# 3_Power.net
KiCad netlist of a schematic drawn in Altium Designer
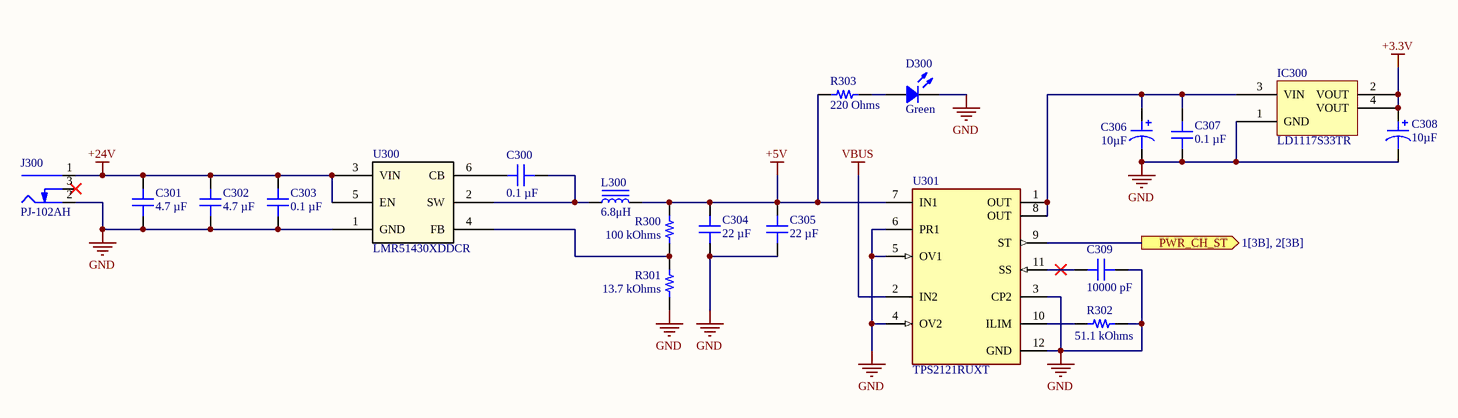
[diagram p0: 3_Power.SchDoc]

(export (version "E")
  (design (tool "Eeschema 10.0.6"))
  (components
    (comp (ref "C300")
      (value "0.1 µF")
      (footprint "CAP 0603_1608")
      (description "CAP CER 0.1UF 25V X7R 0603")
      (fields
        (field (name "PART NUMBER") "CL10B104KA8NNNC")
        (field (name "CAPACITANCE") "0.1 µF")
        (field (name "MANUFACTURER") "Samsung Electro-Mechanics")
      )
      (libsource (lib "Celestial Altium Library - altium_library") (part "Capacitor"))
    )
    (comp (ref "C301")
      (value "4.7 µF")
      (footprint "CAP 1206_3216 - 0.8MM")
      (description "CAP CER 4.7UF 50V X7R 1206")
      (fields
        (field (name "PART NUMBER") "CL31B475KBHNNNE")
        (field (name "CAPACITANCE") "4.7 µF")
        (field (name "MANUFACTURER") "Samsung Electro-Mechanics")
      )
      (libsource (lib "Celestial Altium Library - altium_library") (part "Capacitor"))
    )
    (comp (ref "C302")
      (value "4.7 µF")
      (footprint "CAP 1206_3216 - 0.8MM")
      (description "CAP CER 4.7UF 50V X7R 1206")
      (fields
        (field (name "PART NUMBER") "CL31B475KBHNNNE")
        (field (name "CAPACITANCE") "4.7 µF")
        (field (name "MANUFACTURER") "Samsung Electro-Mechanics")
      )
      (libsource (lib "Celestial Altium Library - altium_library") (part "Capacitor"))
    )
    (comp (ref "C303")
      (value "0.1 µF")
      (footprint "CAP 0603_1608")
      (description "CAP CER 0.1UF 50V X7R 0603")
      (fields
        (field (name "PART NUMBER") "CL10B104KB8NNNC")
        (field (name "CAPACITANCE") "0.1 µF")
        (field (name "MANUFACTURER") "Samsung Electro-Mechanics")
      )
      (libsource (lib "Celestial Altium Library - altium_library") (part "Capacitor"))
    )
    (comp (ref "C304")
      (value "22 µF")
      (footprint "CAP 1210_3225 - 1MM")
      (description "CAP CER 22UF 25V X7R 1210")
      (fields
        (field (name "PART NUMBER") "CL32B226KAJNNNE")
        (field (name "MANUFACTURER") "Samsung Electro-Mechanics")
      )
      (libsource (lib "Celestial Altium Library - altium_library") (part "Capacitor"))
    )
    (comp (ref "C305")
      (value "22 µF")
      (footprint "CAP 1210_3225 - 1MM")
      (description "CAP CER 22UF 25V X7R 1210")
      (fields
        (field (name "PART NUMBER") "CL32B226KAJNNNE")
        (field (name "MANUFACTURER") "Samsung Electro-Mechanics")
      )
      (libsource (lib "Celestial Altium Library - altium_library") (part "Capacitor"))
    )
    (comp (ref "C306")
      (value "10µF")
      (footprint "CAP POL 1206_3216")
      (description "CAP TANT 10UF 10% 16V 1206")
      (fields (field (name "PART NUMBER") "TAJA106K016RNJ") (field (name "MANUFACTURER") "AVX Corporation"))
      (libsource (lib "Celestial Altium Library - altium_library") (part "Polarised Capacitor"))
    )
    (comp (ref "C307")
      (value "0.1 µF")
      (footprint "CAP 0603_1608")
      (description "CAP CER 0.1UF 25V X7R 0603")
      (fields
        (field (name "PART NUMBER") "CL10B104KA8NNNC")
        (field (name "CAPACITANCE") "0.1 µF")
        (field (name "MANUFACTURER") "Samsung Electro-Mechanics")
      )
      (libsource (lib "Celestial Altium Library - altium_library") (part "Capacitor"))
    )
    (comp (ref "C308")
      (value "10µF")
      (footprint "CAP POL 1206_3216")
      (description "CAP TANT 10UF 10% 16V 1206")
      (fields (field (name "PART NUMBER") "TAJA106K016RNJ") (field (name "MANUFACTURER") "AVX Corporation"))
      (libsource (lib "Celestial Altium Library - altium_library") (part "Polarised Capacitor"))
    )
    (comp (ref "C309")
      (value "10000 pF")
      (footprint "CAP 0603_1608")
      (description "CAP CER 10000PF 50V X7R 0603")
      (fields
        (field (name "PART NUMBER") "CL10B103KB8NNNC")
        (field (name "CAPACITANCE") "10000 pF")
        (field (name "MANUFACTURER") "Samsung Electro-Mechanics")
      )
      (libsource (lib "Celestial Altium Library - altium_library") (part "Capacitor"))
    )
    (comp (ref "D300")
      (value "Green")
      (footprint "LED 0603_1608 GREEN")
      (description "LED GREEN CLEAR CHIP SMD")
      (fields (field (name "PART NUMBER") "APT1608CGCK") (field (name "MANUFACTURER") "Kingbright"))
      (libsource (lib "Celestial Altium Library - altium_library") (part "LED"))
    )
    (comp (ref "IC300")
      (value "LD1117S33TR")
      (footprint "ST SOT-223")
      (description "IC REG LINEAR 3.3V 800MA SOT223")
      (fields (field (name "MANUFACTURER") "STMicroelectronics"))
      (libsource (lib "Celestial Altium Library - altium_library") (part "ST LD1117"))
    )
    (comp (ref "J300")
      (value "PJ-102AH")
      (footprint "CUI PJ-102AH")
      (description "CONN PWR JACK 2X5.5MM SOLDER")
      (fields (field (name "MANUFACTURER") "CUI Devices"))
      (libsource (lib "Celestial Altium Library - altium_library") (part "Barrel Connector"))
    )
    (comp (ref "L300")
      (value "SL0624-6R8M")
      (footprint "SL0624-6R8M")
      (description "4A 5A 6.8uH 70mΩ ±20% SMD,7.1x6.6mm Inductors (SMD) ROHS")
      (fields
        (field (name "MANUFACTURER") "TECHFUSE")
        (field (name "TOLERANCE") "±20%")
        (field (name "INDUCTANCE") "6.8μH")
      )
      (libsource (lib "MyLibrary") (part "SL0624-6R8M"))
    )
    (comp (ref "R300")
      (value "100 kOhms")
      (footprint "RES 0603_1608")
      (description "RES SMD 100K OHM 1% 1/10W 0603")
      (fields
        (field (name "PART NUMBER") "ERJ-3EKF1003V")
        (field (name "MANUFACTURER") "Panasonic Electronic Components")
      )
      (libsource (lib "Celestial Altium Library - altium_library") (part "Resistor"))
    )
    (comp (ref "R301")
      (value "13.7 kOhms")
      (footprint "RES 0603_1608")
      (description "RES SMD 13.7K OHM 1% 1/10W 0603")
      (fields
        (field (name "PART NUMBER") "ERJ-3EKF1372V")
        (field (name "MANUFACTURER") "Panasonic Electronic Components")
      )
      (libsource (lib "Celestial Altium Library - altium_library") (part "Resistor"))
    )
    (comp (ref "R302")
      (value "51.1 kOhms")
      (footprint "RES 0603_1608")
      (description "RES SMD 51.1KOHM 0.1% 1/10W 0603")
      (fields
        (field (name "PART NUMBER") "ERA-3AEB5112V")
        (field (name "MANUFACTURER") "Panasonic Electronic Components")
      )
      (libsource (lib "Celestial Altium Library - altium_library") (part "Resistor"))
    )
    (comp (ref "R303")
      (value "220 Ohms")
      (footprint "RES 0603_1608")
      (description "RES SMD 220 OHM 1% 1/5W 0603")
      (fields
        (field (name "PART NUMBER") "ERJ-P03F2200V")
        (field (name "MANUFACTURER") "Panasonic Electronic Components")
      )
      (libsource (lib "Celestial Altium Library - altium_library") (part "Resistor"))
    )
    (comp (ref "U300")
      (value "LMR51430XDDCR")
      (footprint "SOT-23-THIN-6_DDC_TEX")
      (fields (field (name "COPYRIGHT") "Copyright (C) 2026 Ultra Librarian. All rights reserved."))
      (libsource (lib "LMR51430XDDCR") (part "LMR51430XDDCR"))
    )
    (comp (ref "U301")
      (value "TPS2121RUXT")
      (footprint "FP-RUX0012A-MFG")
      (description "PWR MGMT BATTERY MGMT")
      (libsource (lib "Altium Content Vault") (part "f7eeb2b54b908798336ebc03d3325e5"))
    )
  )
  (nets
    (net (code "1") (name "+3.3V") (class "Default")
      (node (ref "C308") (pin "1") (pinfunction "1_1") (pintype "passive"))
      (node (ref "IC300") (pin "2") (pinfunction "VOUT_2") (pintype "passive"))
      (node (ref "IC300") (pin "4") (pinfunction "VOUT_4") (pintype "passive"))
    )
    (net (code "2") (name "+5V") (class "Default")
      (node (ref "C304") (pin "2") (pinfunction "2_2") (pintype "passive"))
      (node (ref "C305") (pin "2") (pinfunction "2_2") (pintype "passive"))
      (node (ref "L300") (pin "2") (pinfunction "2_2") (pintype "passive"))
      (node (ref "R300") (pin "2") (pinfunction "2_2") (pintype "passive"))
      (node (ref "R303") (pin "2") (pinfunction "2_2") (pintype "passive"))
      (node (ref "U301") (pin "7") (pinfunction "IN1_7") (pintype "power_in"))
    )
    (net (code "3") (name "+24V") (class "Default")
      (node (ref "C301") (pin "2") (pinfunction "2_2") (pintype "passive"))
      (node (ref "C302") (pin "2") (pinfunction "2_2") (pintype "passive"))
      (node (ref "C303") (pin "2") (pinfunction "2_2") (pintype "passive"))
      (node (ref "J300") (pin "1") (pinfunction "Centre_1") (pintype "passive"))
      (node (ref "U300") (pin "3") (pinfunction "VIN_3") (pintype "power_in"))
      (node (ref "U300") (pin "5") (pinfunction "EN_5") (pintype "passive"))
    )
    (net (code "4") (name "/PWR_CH_ST") (class "Default")
      (node (ref "U301") (pin "9") (pinfunction "ST_9") (pintype "output"))
    )
    (net (code "5") (name "GND") (class "Default")
      (node (ref "C301") (pin "1") (pinfunction "1_1") (pintype "passive"))
      (node (ref "C302") (pin "1") (pinfunction "1_1") (pintype "passive"))
      (node (ref "C303") (pin "1") (pinfunction "1_1") (pintype "passive"))
      (node (ref "C304") (pin "1") (pinfunction "1_1") (pintype "passive"))
      (node (ref "C305") (pin "1") (pinfunction "1_1") (pintype "passive"))
      (node (ref "C306") (pin "2") (pinfunction "2_2") (pintype "passive"))
      (node (ref "C307") (pin "1") (pinfunction "1_1") (pintype "passive"))
      (node (ref "C308") (pin "2") (pinfunction "2_2") (pintype "passive"))
      (node (ref "C309") (pin "1") (pinfunction "1_1") (pintype "passive"))
      (node (ref "D300") (pin "2") (pinfunction "2_2") (pintype "passive"))
      (node (ref "IC300") (pin "1") (pinfunction "GND_1") (pintype "passive"))
      (node (ref "J300") (pin "2") (pinfunction "Outer_2") (pintype "passive"))
      (node (ref "R301") (pin "1") (pinfunction "1_1") (pintype "passive"))
      (node (ref "R302") (pin "1") (pinfunction "1_1") (pintype "passive"))
      (node (ref "U300") (pin "1") (pinfunction "GND_1") (pintype "power_in"))
      (node (ref "U301") (pin "12") (pinfunction "GND_12") (pintype "power_in"))
      (node (ref "U301") (pin "3") (pinfunction "CP2_3") (pintype "passive"))
      (node (ref "U301") (pin "4") (pinfunction "OV2_4") (pintype "input"))
      (node (ref "U301") (pin "5") (pinfunction "OV1_5") (pintype "input"))
      (node (ref "U301") (pin "6") (pinfunction "PR1_6") (pintype "passive"))
    )
    (net (code "6") (name "Net-(D300-Pad1)") (class "Default")
      (node (ref "D300") (pin "1") (pinfunction "1_1") (pintype "passive"))
      (node (ref "R303") (pin "1") (pinfunction "1_1") (pintype "passive"))
    )
    (net (code "7") (name "Net-(IC300-VIN)") (class "Default")
      (node (ref "C306") (pin "1") (pinfunction "1_1") (pintype "passive"))
      (node (ref "C307") (pin "2") (pinfunction "2_2") (pintype "passive"))
      (node (ref "IC300") (pin "3") (pinfunction "VIN_3") (pintype "passive"))
      (node (ref "U301") (pin "1") (pinfunction "OUT_1") (pintype "power_in"))
      (node (ref "U301") (pin "8") (pinfunction "OUT_8") (pintype "passive"))
    )
    (net (code "8") (name "Net-(U300-CB)") (class "Default")
      (node (ref "C300") (pin "2") (pinfunction "2_2") (pintype "passive"))
      (node (ref "U300") (pin "6") (pinfunction "CB_6") (pintype "power_in"))
    )
    (net (code "9") (name "Net-(U300-FB)") (class "Default")
      (node (ref "R300") (pin "1") (pinfunction "1_1") (pintype "passive"))
      (node (ref "R301") (pin "2") (pinfunction "2_2") (pintype "passive"))
      (node (ref "U300") (pin "4") (pinfunction "FB_4") (pintype "passive"))
    )
    (net (code "10") (name "Net-(U300-SW)") (class "Default")
      (node (ref "C300") (pin "1") (pinfunction "1_1") (pintype "passive"))
      (node (ref "L300") (pin "1") (pinfunction "1_1") (pintype "passive"))
      (node (ref "U300") (pin "2") (pinfunction "SW_2") (pintype "power_in"))
    )
    (net (code "11") (name "Net-(U301-ILIM)") (class "Default")
      (node (ref "R302") (pin "2") (pinfunction "2_2") (pintype "passive"))
      (node (ref "U301") (pin "10") (pinfunction "ILIM_10") (pintype "passive"))
    )
    (net (code "12") (name "Net-(U301-SS)") (class "Default")
      (node (ref "C309") (pin "2") (pinfunction "2_2") (pintype "passive"))
      (node (ref "U301") (pin "11") (pinfunction "SS_11") (pintype "input"))
    )
    (net (code "13") (name "VBUS") (class "Default")
      (node (ref "U301") (pin "2") (pinfunction "IN2_2") (pintype "power_in"))
    )
    (net (code "14") (name "unconnected-(J300-SW-Pad3)") (class "Default")
      (node (ref "J300") (pin "3") (pinfunction "SW_3") (pintype "passive+no_connect"))
    )
  )
)
